# main.net
KiCad netlist of a schematic drawn in Altium Designer
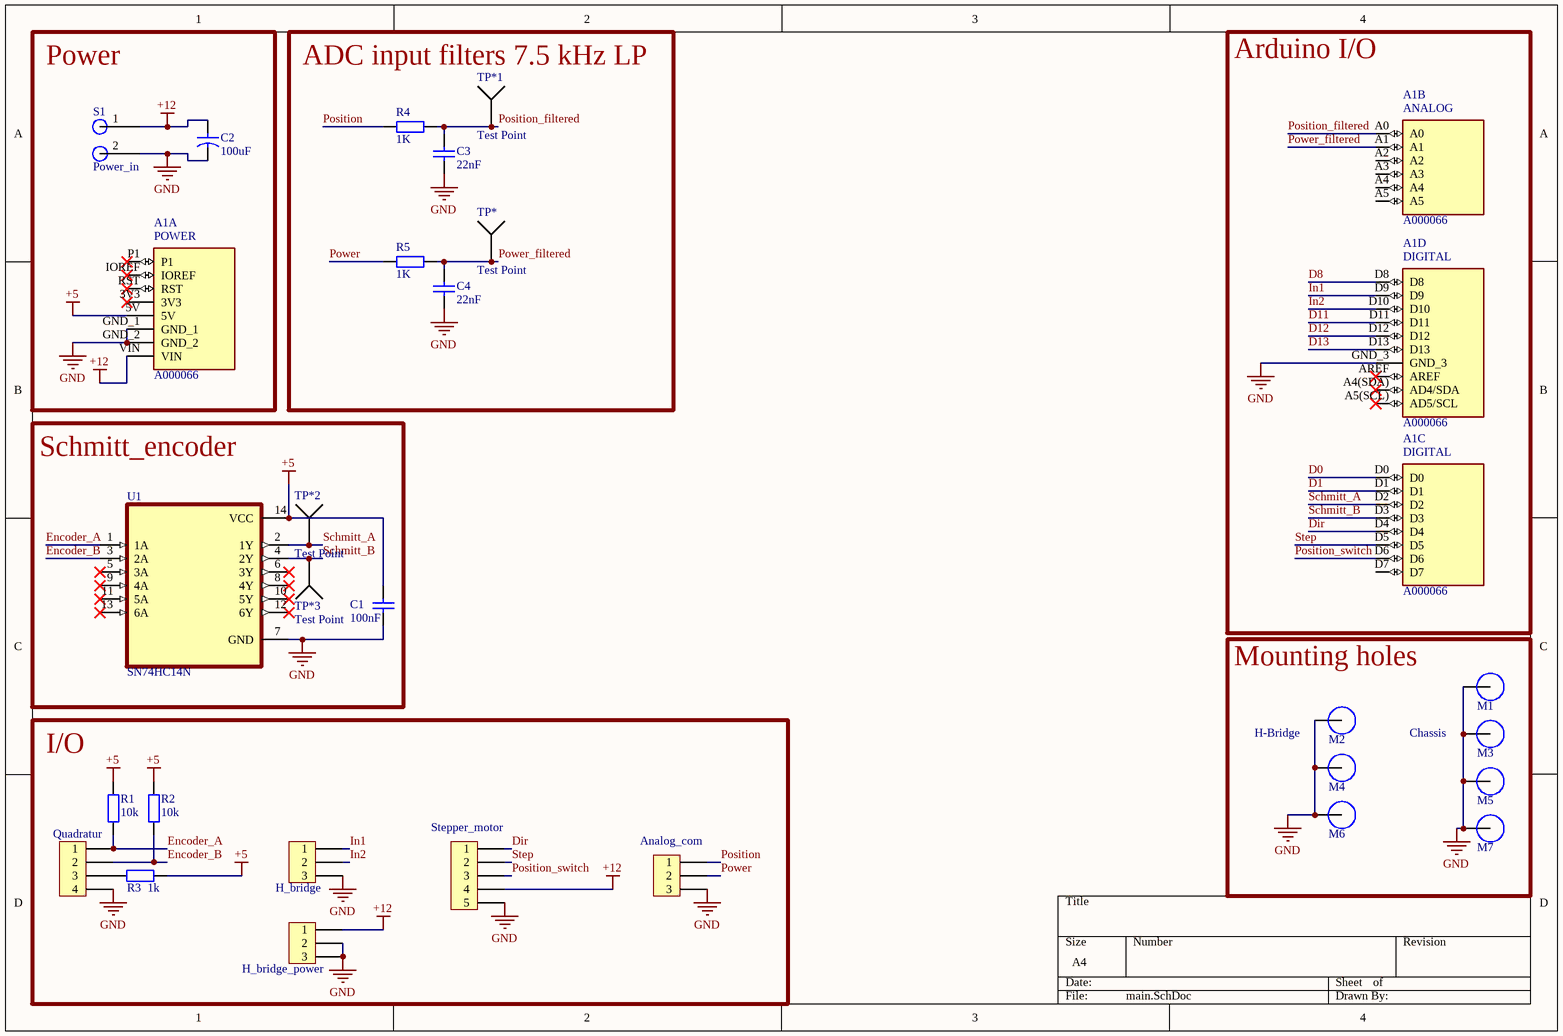
[diagram p0: main.SchDoc]

(export (version "E")
  (design (tool "Eeschema 10.0.6"))
  (components
    (comp (ref "A1")
      (value "A000066")
      (footprint "ARDUINO_A000066")
      (description "Microcontroller board based on the ATmega328P.")
      (fields (field (name "MF") "Arduino") (field (name "MP") "Arduino Uno Rev3"))
      (libsource (lib "A000066(1)") (part "A000066"))
    )
    (comp (ref "Analog_com")
      (value "Header 1x3")
      (footprint "Header 1x3")
      (libsource (lib "AAURacing") (part "Header 1x3"))
    )
    (comp (ref "C1")
      (value "100nF")
      (footprint "Cap-1")
      (fields (field (name "Comment") "Cap"))
      (libsource (lib "AAURacing") (part "Capacitor 1 space"))
    )
    (comp (ref "C2")
      (value "100uF")
      (footprint "Cap Lyt Ø8")
      (fields (field (name "Comment") "Cap"))
      (libsource (lib "AAURacing") (part "Capacitor electrolytic"))
    )
    (comp (ref "C3")
      (value "22nF")
      (footprint "Cap-1")
      (fields (field (name "Comment") "Cap"))
      (libsource (lib "AAURacing") (part "Capacitor 1 space"))
    )
    (comp (ref "C4")
      (value "22nF")
      (footprint "Cap-1")
      (fields (field (name "Comment") "Cap"))
      (libsource (lib "AAURacing") (part "Capacitor 1 space"))
    )
    (comp (ref "H_bridge")
      (value "Header 1x3")
      (footprint "Header 1x3")
      (libsource (lib "AAURacing") (part "Header 1x3"))
    )
    (comp (ref "H_bridge_power")
      (value "Header 1x3")
      (footprint "Header 1x3")
      (libsource (lib "AAURacing") (part "Header 1x3"))
    )
    (comp (ref "M1")
      (value "Screw Hole")
      (footprint "M3 Hole")
      (libsource (lib "AAURacing") (part "Screw Hole"))
    )
    (comp (ref "M2")
      (value "Screw Hole")
      (footprint "M3 Hole")
      (libsource (lib "AAURacing") (part "Screw Hole"))
    )
    (comp (ref "M3")
      (value "Screw Hole")
      (footprint "M3 Hole")
      (libsource (lib "AAURacing") (part "Screw Hole"))
    )
    (comp (ref "M4")
      (value "Screw Hole")
      (footprint "M3 Hole")
      (libsource (lib "AAURacing") (part "Screw Hole"))
    )
    (comp (ref "M5")
      (value "Screw Hole")
      (footprint "M3 Hole")
      (libsource (lib "AAURacing") (part "Screw Hole"))
    )
    (comp (ref "M6")
      (value "Screw Hole")
      (footprint "M3 Hole")
      (libsource (lib "AAURacing") (part "Screw Hole"))
    )
    (comp (ref "M7")
      (value "Screw Hole")
      (footprint "M3 Hole")
      (libsource (lib "AAURacing") (part "Screw Hole"))
    )
    (comp (ref "Quadratur")
      (value "Header 1x4")
      (footprint "Header 1x4")
      (libsource (lib "AAURacing") (part "Header 1x4"))
    )
    (comp (ref "R1")
      (value "10k")
      (footprint "RES THT 9mm")
      (fields (field (name "Comment") "Resistor"))
      (libsource (lib "AAURacing") (part "Resistor"))
    )
    (comp (ref "R2")
      (value "10k")
      (footprint "RES THT 9mm")
      (fields (field (name "Comment") "Resistor"))
      (libsource (lib "AAURacing") (part "Resistor"))
    )
    (comp (ref "R3")
      (value "1k")
      (footprint "RES THT 9mm")
      (fields (field (name "Comment") "Resistor"))
      (libsource (lib "AAURacing") (part "Resistor"))
    )
    (comp (ref "R4")
      (value "1K")
      (footprint "RES THT 9mm")
      (fields (field (name "Comment") "Resistor"))
      (libsource (lib "AAURacing") (part "Resistor"))
    )
    (comp (ref "R5")
      (value "1K")
      (footprint "RES THT 9mm")
      (fields (field (name "Comment") "Resistor"))
      (libsource (lib "AAURacing") (part "Resistor"))
    )
    (comp (ref "S1") (value "Power_in") (footprint "Screw-2") (libsource (lib "AAURacing") (part "Screw 2")))
    (comp (ref "Stepper_motor")
      (value "Header 1x5")
      (footprint "Header 1x5")
      (libsource (lib "AAURacing") (part "Header 1x5"))
    )
    (comp (ref "TP*")
      (value "Test Point")
      (footprint "TP_loop_pin_1249")
      (libsource (lib "AAURacing") (part "Test Point"))
    )
    (comp (ref "TP*1")
      (value "Test Point")
      (footprint "TP_loop_pin_1249")
      (libsource (lib "AAURacing") (part "Test Point"))
    )
    (comp (ref "TP*2")
      (value "Test Point")
      (footprint "TP_loop_pin_1249")
      (libsource (lib "AAURacing") (part "Test Point"))
    )
    (comp (ref "TP*3")
      (value "Test Point")
      (footprint "TP_loop_pin_1249")
      (libsource (lib "AAURacing") (part "Test Point"))
    )
    (comp (ref "U1")
      (value "SN74HC14N")
      (footprint "DIP794W45P254L1969H508Q14")
      (description "6-ch, 2-V to 6-V inverters with Schmitt-Trigger inputs")
      (fields (field (name "MF") "Texas Instruments"))
      (libsource (lib "SN74HC14N") (part "SN74HC14N"))
    )
  )
  (nets
    (net (code "1") (name "+5") (class "Default")
      (node (ref "A1") (pin "5V") (pinfunction "5V_5V") (pintype "power_in"))
      (node (ref "C1") (pin "2") (pinfunction "g_2") (pintype "passive"))
      (node (ref "R1") (pin "2") (pinfunction "2_2") (pintype "passive"))
      (node (ref "R2") (pin "2") (pinfunction "2_2") (pintype "passive"))
      (node (ref "R3") (pin "1") (pinfunction "1_1") (pintype "passive"))
      (node (ref "U1") (pin "14") (pinfunction "VCC_14") (pintype "power_in"))
    )
    (net (code "2") (name "+12") (class "Default")
      (node (ref "A1") (pin "VIN") (pinfunction "VIN_VIN") (pintype "power_in"))
      (node (ref "C2") (pin "1") (pinfunction "1_1") (pintype "passive"))
      (node (ref "H_bridge_power") (pin "1") (pinfunction "1_1") (pintype "passive"))
      (node (ref "S1") (pin "1") (pinfunction "1_1") (pintype "passive"))
      (node (ref "Stepper_motor") (pin "4") (pinfunction "4_4") (pintype "passive"))
    )
    (net (code "3") (name "/D0") (class "Default")
      (node (ref "A1") (pin "D0") (pinfunction "D0_D0") (pintype "bidirectional"))
    )
    (net (code "4") (name "/D1") (class "Default")
      (node (ref "A1") (pin "D1") (pinfunction "D1_D1") (pintype "bidirectional"))
    )
    (net (code "5") (name "/D8") (class "Default")
      (node (ref "A1") (pin "D8") (pinfunction "D8_D8") (pintype "bidirectional"))
    )
    (net (code "6") (name "/D11") (class "Default")
      (node (ref "A1") (pin "D11") (pinfunction "D11_D11") (pintype "bidirectional"))
    )
    (net (code "7") (name "/D12") (class "Default")
      (node (ref "A1") (pin "D12") (pinfunction "D12_D12") (pintype "bidirectional"))
    )
    (net (code "8") (name "/D13") (class "Default")
      (node (ref "A1") (pin "D13") (pinfunction "D13_D13") (pintype "bidirectional"))
    )
    (net (code "9") (name "/Dir") (class "Default")
      (node (ref "A1") (pin "D4") (pinfunction "D4_D4") (pintype "bidirectional"))
      (node (ref "Stepper_motor") (pin "1") (pinfunction "1_1") (pintype "passive"))
    )
    (net (code "10") (name "/Encoder_A") (class "Default")
      (node (ref "Quadratur") (pin "1") (pinfunction "1_1") (pintype "passive"))
      (node (ref "R1") (pin "1") (pinfunction "1_1") (pintype "passive"))
      (node (ref "U1") (pin "1") (pinfunction "1A_1") (pintype "input"))
    )
    (net (code "11") (name "/Encoder_B") (class "Default")
      (node (ref "Quadratur") (pin "2") (pinfunction "2_2") (pintype "passive"))
      (node (ref "R2") (pin "1") (pinfunction "1_1") (pintype "passive"))
      (node (ref "U1") (pin "3") (pinfunction "2A_3") (pintype "input"))
    )
    (net (code "12") (name "/In1") (class "Default")
      (node (ref "A1") (pin "D9") (pinfunction "D9_D9") (pintype "bidirectional"))
      (node (ref "H_bridge") (pin "1") (pinfunction "1_1") (pintype "passive"))
    )
    (net (code "13") (name "/In2") (class "Default")
      (node (ref "A1") (pin "D10") (pinfunction "D10_D10") (pintype "bidirectional"))
      (node (ref "H_bridge") (pin "2") (pinfunction "2_2") (pintype "passive"))
    )
    (net (code "14") (name "/Position") (class "Default")
      (node (ref "Analog_com") (pin "1") (pinfunction "1_1") (pintype "passive"))
      (node (ref "R4") (pin "1") (pinfunction "1_1") (pintype "passive"))
    )
    (net (code "15") (name "/Position_filtered") (class "Default")
      (node (ref "A1") (pin "A0") (pinfunction "A0_A0") (pintype "bidirectional"))
      (node (ref "C3") (pin "2") (pinfunction "g_2") (pintype "passive"))
      (node (ref "R4") (pin "2") (pinfunction "2_2") (pintype "passive"))
      (node (ref "TP*1") (pin "TP") (pinfunction "1_TP") (pintype "passive"))
    )
    (net (code "16") (name "/Position_switch") (class "Default")
      (node (ref "A1") (pin "D6") (pinfunction "D6_D6") (pintype "bidirectional"))
      (node (ref "Stepper_motor") (pin "3") (pinfunction "3_3") (pintype "passive"))
    )
    (net (code "17") (name "/Power") (class "Default")
      (node (ref "Analog_com") (pin "2") (pinfunction "2_2") (pintype "passive"))
      (node (ref "R5") (pin "1") (pinfunction "1_1") (pintype "passive"))
    )
    (net (code "18") (name "/Power_filtered") (class "Default")
      (node (ref "A1") (pin "A1") (pinfunction "A1_A1") (pintype "bidirectional"))
      (node (ref "C4") (pin "2") (pinfunction "g_2") (pintype "passive"))
      (node (ref "R5") (pin "2") (pinfunction "2_2") (pintype "passive"))
      (node (ref "TP*") (pin "TP") (pinfunction "1_TP") (pintype "passive"))
    )
    (net (code "19") (name "/Schmitt_A") (class "Default")
      (node (ref "A1") (pin "D2") (pinfunction "D2_D2") (pintype "bidirectional"))
      (node (ref "TP*2") (pin "TP") (pinfunction "1_TP") (pintype "passive"))
      (node (ref "U1") (pin "2") (pinfunction "1Y_2") (pintype "output"))
    )
    (net (code "20") (name "/Schmitt_B") (class "Default")
      (node (ref "A1") (pin "D3") (pinfunction "D3_D3") (pintype "bidirectional"))
      (node (ref "TP*3") (pin "TP") (pinfunction "1_TP") (pintype "passive"))
      (node (ref "U1") (pin "4") (pinfunction "2Y_4") (pintype "output"))
    )
    (net (code "21") (name "/Step") (class "Default")
      (node (ref "A1") (pin "D5") (pinfunction "D5_D5") (pintype "bidirectional"))
      (node (ref "Stepper_motor") (pin "2") (pinfunction "2_2") (pintype "passive"))
    )
    (net (code "22") (name "GND") (class "Default")
      (node (ref "A1") (pin "GND_1") (pinfunction "GND_1_GND_1") (pintype "power_in"))
      (node (ref "A1") (pin "GND_2") (pinfunction "GND_2_GND_2") (pintype "power_in"))
      (node (ref "A1") (pin "GND_3") (pinfunction "GND_3_GND_3") (pintype "power_in"))
      (node (ref "Analog_com") (pin "3") (pinfunction "3_3") (pintype "passive"))
      (node (ref "C1") (pin "1") (pinfunction "1_1") (pintype "passive"))
      (node (ref "C2") (pin "2") (pinfunction "g_2") (pintype "passive"))
      (node (ref "C3") (pin "1") (pinfunction "1_1") (pintype "passive"))
      (node (ref "C4") (pin "1") (pinfunction "1_1") (pintype "passive"))
      (node (ref "H_bridge") (pin "3") (pinfunction "3_3") (pintype "passive"))
      (node (ref "H_bridge_power") (pin "2") (pinfunction "2_2") (pintype "passive"))
      (node (ref "H_bridge_power") (pin "3") (pinfunction "3_3") (pintype "passive"))
      (node (ref "M1") (pin "1") (pinfunction "1_1") (pintype "passive"))
      (node (ref "M2") (pin "1") (pinfunction "1_1") (pintype "passive"))
      (node (ref "M3") (pin "1") (pinfunction "1_1") (pintype "passive"))
      (node (ref "M4") (pin "1") (pinfunction "1_1") (pintype "passive"))
      (node (ref "M5") (pin "1") (pinfunction "1_1") (pintype "passive"))
      (node (ref "M6") (pin "1") (pinfunction "1_1") (pintype "passive"))
      (node (ref "M7") (pin "1") (pinfunction "1_1") (pintype "passive"))
      (node (ref "Quadratur") (pin "4") (pinfunction "4_4") (pintype "passive"))
      (node (ref "S1") (pin "2") (pinfunction "2_2") (pintype "passive"))
      (node (ref "Stepper_motor") (pin "5") (pinfunction "5_5") (pintype "passive"))
      (node (ref "U1") (pin "7") (pinfunction "GND_7") (pintype "power_in"))
    )
    (net (code "23") (name "Net-(Quadratur-Pad3)") (class "Default")
      (node (ref "Quadratur") (pin "3") (pinfunction "3_3") (pintype "passive"))
      (node (ref "R3") (pin "2") (pinfunction "2_2") (pintype "passive"))
    )
    (net (code "24") (name "unconnected-(A1-Pad3V3)") (class "Default")
      (node (ref "A1") (pin "3V3") (pinfunction "3V3_3V3") (pintype "power_in+no_connect"))
    )
    (net (code "25") (name "unconnected-(A1-PadA2)") (class "Default")
      (node (ref "A1") (pin "A2") (pinfunction "A2_A2") (pintype "bidirectional"))
    )
    (net (code "26") (name "unconnected-(A1-PadA3)") (class "Default")
      (node (ref "A1") (pin "A3") (pinfunction "A3_A3") (pintype "bidirectional"))
    )
    (net (code "27") (name "unconnected-(A1-PadA4)") (class "Default")
      (node (ref "A1") (pin "A4") (pinfunction "A4_A4") (pintype "bidirectional"))
    )
    (net (code "28") (name "unconnected-(A1-PadA5)") (class "Default")
      (node (ref "A1") (pin "A5") (pinfunction "A5_A5") (pintype "bidirectional"))
    )
    (net (code "29") (name "unconnected-(A1-PadAREF)") (class "Default")
      (node (ref "A1") (pin "AREF") (pinfunction "AREF_AREF") (pintype "bidirectional+no_connect"))
    )
    (net (code "30") (name "unconnected-(A1-PadD7)") (class "Default")
      (node (ref "A1") (pin "D7") (pinfunction "D7_D7") (pintype "bidirectional"))
    )
    (net (code "31") (name "unconnected-(A1-PadIOREF)") (class "Default")
      (node (ref "A1") (pin "IOREF") (pinfunction "IOREF_IOREF") (pintype "bidirectional+no_connect"))
    )
    (net (code "32") (name "unconnected-(A1-PadP1)") (class "Default")
      (node (ref "A1") (pin "P1") (pinfunction "P1_P1") (pintype "bidirectional+no_connect"))
    )
    (net (code "33") (name "unconnected-(A1-PadRST)") (class "Default")
      (node (ref "A1") (pin "RST") (pinfunction "RST_RST") (pintype "bidirectional+no_connect"))
    )
    (net (code "34") (name "unconnected-(A1D-AD4{slash}SDA-PadA4(SDA))") (class "Default")
      (node (ref "A1") (pin "A4(SDA)") (pinfunction "AD4/SDA_A4(SDA)") (pintype "bidirectional+no_connect"))
    )
    (net (code "35") (name "unconnected-(A1D-AD5{slash}SCL-PadA5(SCL))") (class "Default")
      (node (ref "A1") (pin "A5(SCL)") (pinfunction "AD5/SCL_A5(SCL)") (pintype "bidirectional+no_connect"))
    )
    (net (code "36") (name "unconnected-(U1-3A-Pad5)") (class "Default")
      (node (ref "U1") (pin "5") (pinfunction "3A_5") (pintype "input+no_connect"))
    )
    (net (code "37") (name "unconnected-(U1-3Y-Pad6)") (class "Default")
      (node (ref "U1") (pin "6") (pinfunction "3Y_6") (pintype "output+no_connect"))
    )
    (net (code "38") (name "unconnected-(U1-4A-Pad9)") (class "Default")
      (node (ref "U1") (pin "9") (pinfunction "4A_9") (pintype "input+no_connect"))
    )
    (net (code "39") (name "unconnected-(U1-4Y-Pad8)") (class "Default")
      (node (ref "U1") (pin "8") (pinfunction "4Y_8") (pintype "output+no_connect"))
    )
    (net (code "40") (name "unconnected-(U1-5A-Pad11)") (class "Default")
      (node (ref "U1") (pin "11") (pinfunction "5A_11") (pintype "input+no_connect"))
    )
    (net (code "41") (name "unconnected-(U1-5Y-Pad10)") (class "Default")
      (node (ref "U1") (pin "10") (pinfunction "5Y_10") (pintype "output+no_connect"))
    )
    (net (code "42") (name "unconnected-(U1-6A-Pad13)") (class "Default")
      (node (ref "U1") (pin "13") (pinfunction "6A_13") (pintype "input+no_connect"))
    )
    (net (code "43") (name "unconnected-(U1-6Y-Pad12)") (class "Default")
      (node (ref "U1") (pin "12") (pinfunction "6Y_12") (pintype "output+no_connect"))
    )
  )
)
